# V1_0.net
KiCad netlist of a schematic drawn in Altium Designer
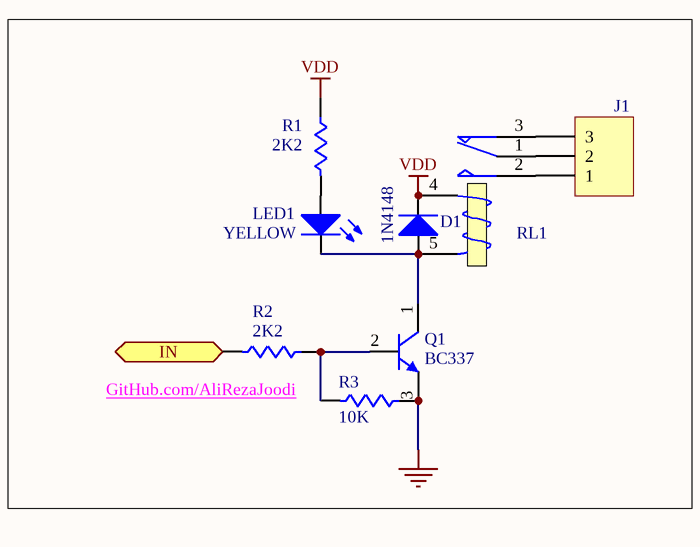
[diagram p0: V1.0.SchDoc]

(export (version "E")
  (design (tool "Eeschema 10.0.6"))
  (components
    (comp (ref "D1")
      (value "1N4148")
      (footprint "DIODE0.4_Glass")
      (description "Default Diode")
      (fields (field (name "MANUFACTURER") "Generic Components") (field (name "PUBLISHER") "Altium Limited"))
      (libsource (lib "Miscellaneous Devices") (part "Diode"))
    )
    (comp (ref "J1")
      (value "3PIN")
      (footprint "Fonics_3PIN_1")
      (description "Header, 3-Pin")
      (fields (field (name "MANUFACTURER") "Generic Components") (field (name "PUBLISHER") "Altium Limited"))
      (libsource (lib "Miscellaneous Connectors") (part "Header 3"))
    )
    (comp (ref "LED1")
      (value "YELLOW")
      (footprint "LED_5mm")
      (description "Typical INFRARED GaAs LED")
      (fields (field (name "MANUFACTURER") "Generic Components") (field (name "PUBLISHER") "Altium Limited"))
      (libsource (lib "my Libraries") (part "Optical Transmitter"))
    )
    (comp (ref "Q1")
      (value "BC337")
      (footprint "TO92C")
      (description "NPN Bipolar Transistor")
      (fields (field (name "MANUFACTURER") "Generic Components") (field (name "PUBLISHER") "Altium Limited"))
      (libsource (lib "Miscellaneous Devices") (part "NPN"))
    )
    (comp (ref "R1")
      (value "2K2")
      (footprint "AXIAL-0.4")
      (description "Resistor")
      (fields (field (name "MANUFACTURER") "Generic Components") (field (name "PUBLISHER") "Altium Limited"))
      (libsource (lib "Miscellaneous Devices") (part "Res1"))
    )
    (comp (ref "R2")
      (value "2K2")
      (footprint "AXIAL-0.4")
      (description "Resistor")
      (fields (field (name "MANUFACTURER") "Generic Components") (field (name "PUBLISHER") "Altium Limited"))
      (libsource (lib "Miscellaneous Devices") (part "Res1"))
    )
    (comp (ref "R3")
      (value "10K")
      (footprint "AXIAL-0.4")
      (description "Resistor")
      (fields (field (name "MANUFACTURER") "Generic Components") (field (name "PUBLISHER") "Altium Limited"))
      (libsource (lib "Miscellaneous Devices") (part "Res1"))
    )
    (comp (ref "RL1")
      (value "12V")
      (footprint "RELAY-SPDT-1")
      (description "SPDT Relay")
      (fields (field (name "MANUFACTURER") "Generic Components") (field (name "PUBLISHER") "Altium Limited"))
      (libsource (lib "Miscellaneous Devices") (part "Relay-SPDT_2"))
    )
  )
  (nets
    (net (code "1") (name "/IN") (class "Default")
      (node (ref "R2") (pin "2") (pinfunction "2_2") (pintype "passive"))
    )
    (net (code "2") (name "GND") (class "Default")
      (node (ref "Q1") (pin "3") (pinfunction "E_3") (pintype "passive"))
      (node (ref "R3") (pin "1") (pinfunction "1_1") (pintype "passive"))
    )
    (net (code "3") (name "Net-(D1-A)") (class "Default")
      (node (ref "D1") (pin "1") (pinfunction "A_1") (pintype "passive"))
      (node (ref "LED1") (pin "2") (pinfunction "K_2") (pintype "passive"))
      (node (ref "Q1") (pin "1") (pinfunction "C_1") (pintype "passive"))
      (node (ref "RL1") (pin "5") (pinfunction "T2_5") (pintype "passive"))
    )
    (net (code "4") (name "Net-(LED1-A)") (class "Default")
      (node (ref "LED1") (pin "1") (pinfunction "A_1") (pintype "passive"))
      (node (ref "R1") (pin "2") (pinfunction "2_2") (pintype "passive"))
    )
    (net (code "5") (name "Net-(Q1-B)") (class "Default")
      (node (ref "Q1") (pin "2") (pinfunction "B_2") (pintype "passive"))
      (node (ref "R2") (pin "1") (pinfunction "1_1") (pintype "passive"))
      (node (ref "R3") (pin "2") (pinfunction "2_2") (pintype "passive"))
    )
    (net (code "6") (name "Net-(RL1-COM)") (class "Default")
      (node (ref "J1") (pin "2") (pinfunction "2_2") (pintype "passive"))
      (node (ref "RL1") (pin "1") (pinfunction "COM_1") (pintype "passive"))
    )
    (net (code "7") (name "Net-(RL1-NC)") (class "Default")
      (node (ref "J1") (pin "3") (pinfunction "3_3") (pintype "passive"))
      (node (ref "RL1") (pin "3") (pinfunction "NC_3") (pintype "passive"))
    )
    (net (code "8") (name "Net-(RL1-NO)") (class "Default")
      (node (ref "J1") (pin "1") (pinfunction "1_1") (pintype "passive"))
      (node (ref "RL1") (pin "2") (pinfunction "NO_2") (pintype "passive"))
    )
    (net (code "9") (name "VDD") (class "Default")
      (node (ref "D1") (pin "2") (pinfunction "K_2") (pintype "passive"))
      (node (ref "R1") (pin "1") (pinfunction "1_1") (pintype "passive"))
      (node (ref "RL1") (pin "4") (pinfunction "T1_4") (pintype "passive"))
    )
  )
)
